# 3V3REGULATOR.net
KiCad netlist of a schematic drawn in Altium Designer
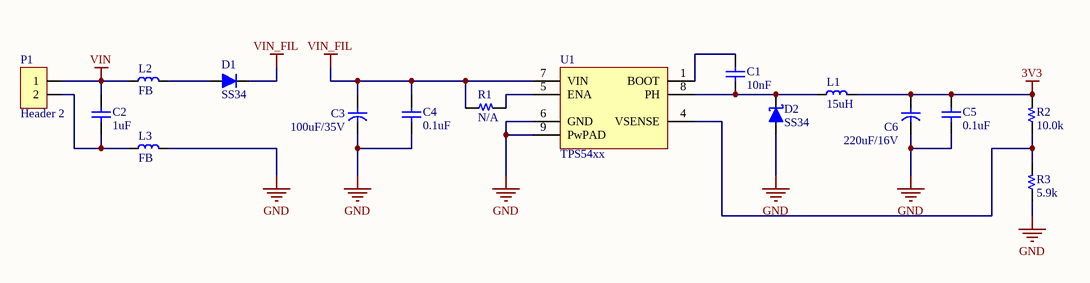
[diagram p0: 3V3REGULATOR.SchDoc]

(export (version "E")
  (design (tool "Eeschema 10.0.6"))
  (components
    (comp (ref "C1")
      (value "10nF")
      (footprint "C 1206")
      (description "Capacitor non-pol")
      (libsource (lib "chipfc_libs") (part "Capacitor NP"))
    )
    (comp (ref "C2")
      (value "1uF")
      (footprint "C 1206")
      (description "Capacitor non-pol")
      (libsource (lib "chipfc_libs") (part "Capacitor NP"))
    )
    (comp (ref "C3")
      (value "100uF/35V")
      (footprint "C SMD ALU (D)")
      (description "Capacitor pol")
      (libsource (lib "chipfc_libs") (part "Capacitor"))
    )
    (comp (ref "C4")
      (value "0.1uF")
      (footprint "C 1206")
      (description "Capacitor non-pol")
      (libsource (lib "chipfc_libs") (part "Capacitor NP"))
    )
    (comp (ref "C5")
      (value "0.1uF")
      (footprint "C 1206")
      (description "Capacitor non-pol")
      (libsource (lib "chipfc_libs") (part "Capacitor NP"))
    )
    (comp (ref "C6")
      (value "220uF/16V")
      (footprint "C SMD ALU (D)")
      (description "Capacitor pol")
      (libsource (lib "chipfc_libs") (part "Capacitor"))
    )
    (comp (ref "D1")
      (value "SS34")
      (footprint "SOD123")
      (description "Default Diode")
      (libsource (lib "chipfc_libs") (part "Diode"))
    )
    (comp (ref "D2")
      (value "SS34")
      (footprint "SOD123")
      (description "Schottky Diode")
      (libsource (lib "chipfc_libs") (part "Diode Schottky"))
    )
    (comp (ref "L1")
      (value "15uH")
      (footprint "Inductor SMD 6.5x6.5x3.0")
      (description "Inductor")
      (libsource (lib "chipfc_libs") (part "Inductor"))
    )
    (comp (ref "L2")
      (value "FB")
      (footprint "L 0805 (2012)")
      (description "Inductor")
      (libsource (lib "chipfc_libs") (part "Inductor"))
    )
    (comp (ref "L3")
      (value "FB")
      (footprint "L 0805 (2012)")
      (description "Inductor")
      (libsource (lib "chipfc_libs") (part "Inductor"))
    )
    (comp (ref "P1")
      (value "Header 2")
      (footprint "HDR/Terminal/2")
      (description "Header, 2-Pin")
      (libsource (lib "connectors") (part "Header 2"))
    )
    (comp (ref "R1")
      (value "N/A")
      (footprint "R 0603")
      (description "Resistor")
      (libsource (lib "chipfc_libs") (part "Resistor"))
    )
    (comp (ref "R2")
      (value "10.0k")
      (footprint "R 0603")
      (description "Resistor")
      (libsource (lib "chipfc_libs") (part "Resistor"))
    )
    (comp (ref "R3")
      (value "5.9k")
      (footprint "R 0603")
      (description "Resistor")
      (libsource (lib "chipfc_libs") (part "Resistor"))
    )
    (comp (ref "U1")
      (value "TPS54xx")
      (footprint "SOIC-8 EP")
      (description "3/5A, Wide input range, Step-down SWIFT DC-DC Converter")
      (libsource (lib "chipfc_libs") (part "TPS54xx"))
    )
  )
  (nets
    (net (code "1") (name "3V3") (class "Default")
      (node (ref "C5") (pin "1") (pinfunction "1_1") (pintype "passive"))
      (node (ref "C6") (pin "1") (pinfunction "1_1") (pintype "passive"))
      (node (ref "L1") (pin "2") (pinfunction "2_2") (pintype "passive"))
      (node (ref "R2") (pin "2") (pinfunction "2_2") (pintype "passive"))
    )
    (net (code "2") (name "GND") (class "Default")
      (node (ref "C3") (pin "2") (pinfunction "2_2") (pintype "passive"))
      (node (ref "C4") (pin "2") (pinfunction "2_2") (pintype "passive"))
      (node (ref "C5") (pin "2") (pinfunction "2_2") (pintype "passive"))
      (node (ref "C6") (pin "2") (pinfunction "2_2") (pintype "passive"))
      (node (ref "D2") (pin "1") (pinfunction "A_1") (pintype "passive"))
      (node (ref "L3") (pin "2") (pinfunction "2_2") (pintype "passive"))
      (node (ref "R3") (pin "1") (pinfunction "1_1") (pintype "passive"))
      (node (ref "U1") (pin "6") (pinfunction "GND_6") (pintype "passive"))
      (node (ref "U1") (pin "9") (pinfunction "PwPAD_9") (pintype "passive"))
    )
    (net (code "3") (name "Net-(C2-Pad2)") (class "Default")
      (node (ref "C2") (pin "2") (pinfunction "2_2") (pintype "passive"))
      (node (ref "L3") (pin "1") (pinfunction "1_1") (pintype "passive"))
      (node (ref "P1") (pin "2") (pinfunction "2_2") (pintype "passive"))
    )
    (net (code "4") (name "Net-(D1-A)") (class "Default")
      (node (ref "D1") (pin "1") (pinfunction "A_1") (pintype "passive"))
      (node (ref "L2") (pin "2") (pinfunction "2_2") (pintype "passive"))
    )
    (net (code "5") (name "Net-(D2-K)") (class "Default")
      (node (ref "C1") (pin "2") (pinfunction "2_2") (pintype "passive"))
      (node (ref "D2") (pin "2") (pinfunction "K_2") (pintype "passive"))
      (node (ref "L1") (pin "1") (pinfunction "1_1") (pintype "passive"))
      (node (ref "U1") (pin "8") (pinfunction "PH_8") (pintype "passive"))
    )
    (net (code "6") (name "Net-(U1-BOOT)") (class "Default")
      (node (ref "C1") (pin "1") (pinfunction "1_1") (pintype "passive"))
      (node (ref "U1") (pin "1") (pinfunction "BOOT_1") (pintype "passive"))
    )
    (net (code "7") (name "Net-(U1-ENA)") (class "Default")
      (node (ref "R1") (pin "2") (pinfunction "2_2") (pintype "passive"))
      (node (ref "U1") (pin "5") (pinfunction "ENA_5") (pintype "passive"))
    )
    (net (code "8") (name "Net-(U1-VSENSE)") (class "Default")
      (node (ref "R2") (pin "1") (pinfunction "1_1") (pintype "passive"))
      (node (ref "R3") (pin "2") (pinfunction "2_2") (pintype "passive"))
      (node (ref "U1") (pin "4") (pinfunction "VSENSE_4") (pintype "passive"))
    )
    (net (code "9") (name "VIN") (class "Default")
      (node (ref "C2") (pin "1") (pinfunction "1_1") (pintype "passive"))
      (node (ref "L2") (pin "1") (pinfunction "1_1") (pintype "passive"))
      (node (ref "P1") (pin "1") (pinfunction "1_1") (pintype "passive"))
    )
    (net (code "10") (name "VIN_FIL") (class "Default")
      (node (ref "C3") (pin "1") (pinfunction "1_1") (pintype "passive"))
      (node (ref "C4") (pin "1") (pinfunction "1_1") (pintype "passive"))
      (node (ref "D1") (pin "2") (pinfunction "K_2") (pintype "passive"))
      (node (ref "R1") (pin "1") (pinfunction "1_1") (pintype "passive"))
      (node (ref "U1") (pin "7") (pinfunction "VIN_7") (pintype "passive"))
    )
  )
)
